# 10-RF_WIFI.net
KiCad netlist of a schematic drawn in Altium Designer
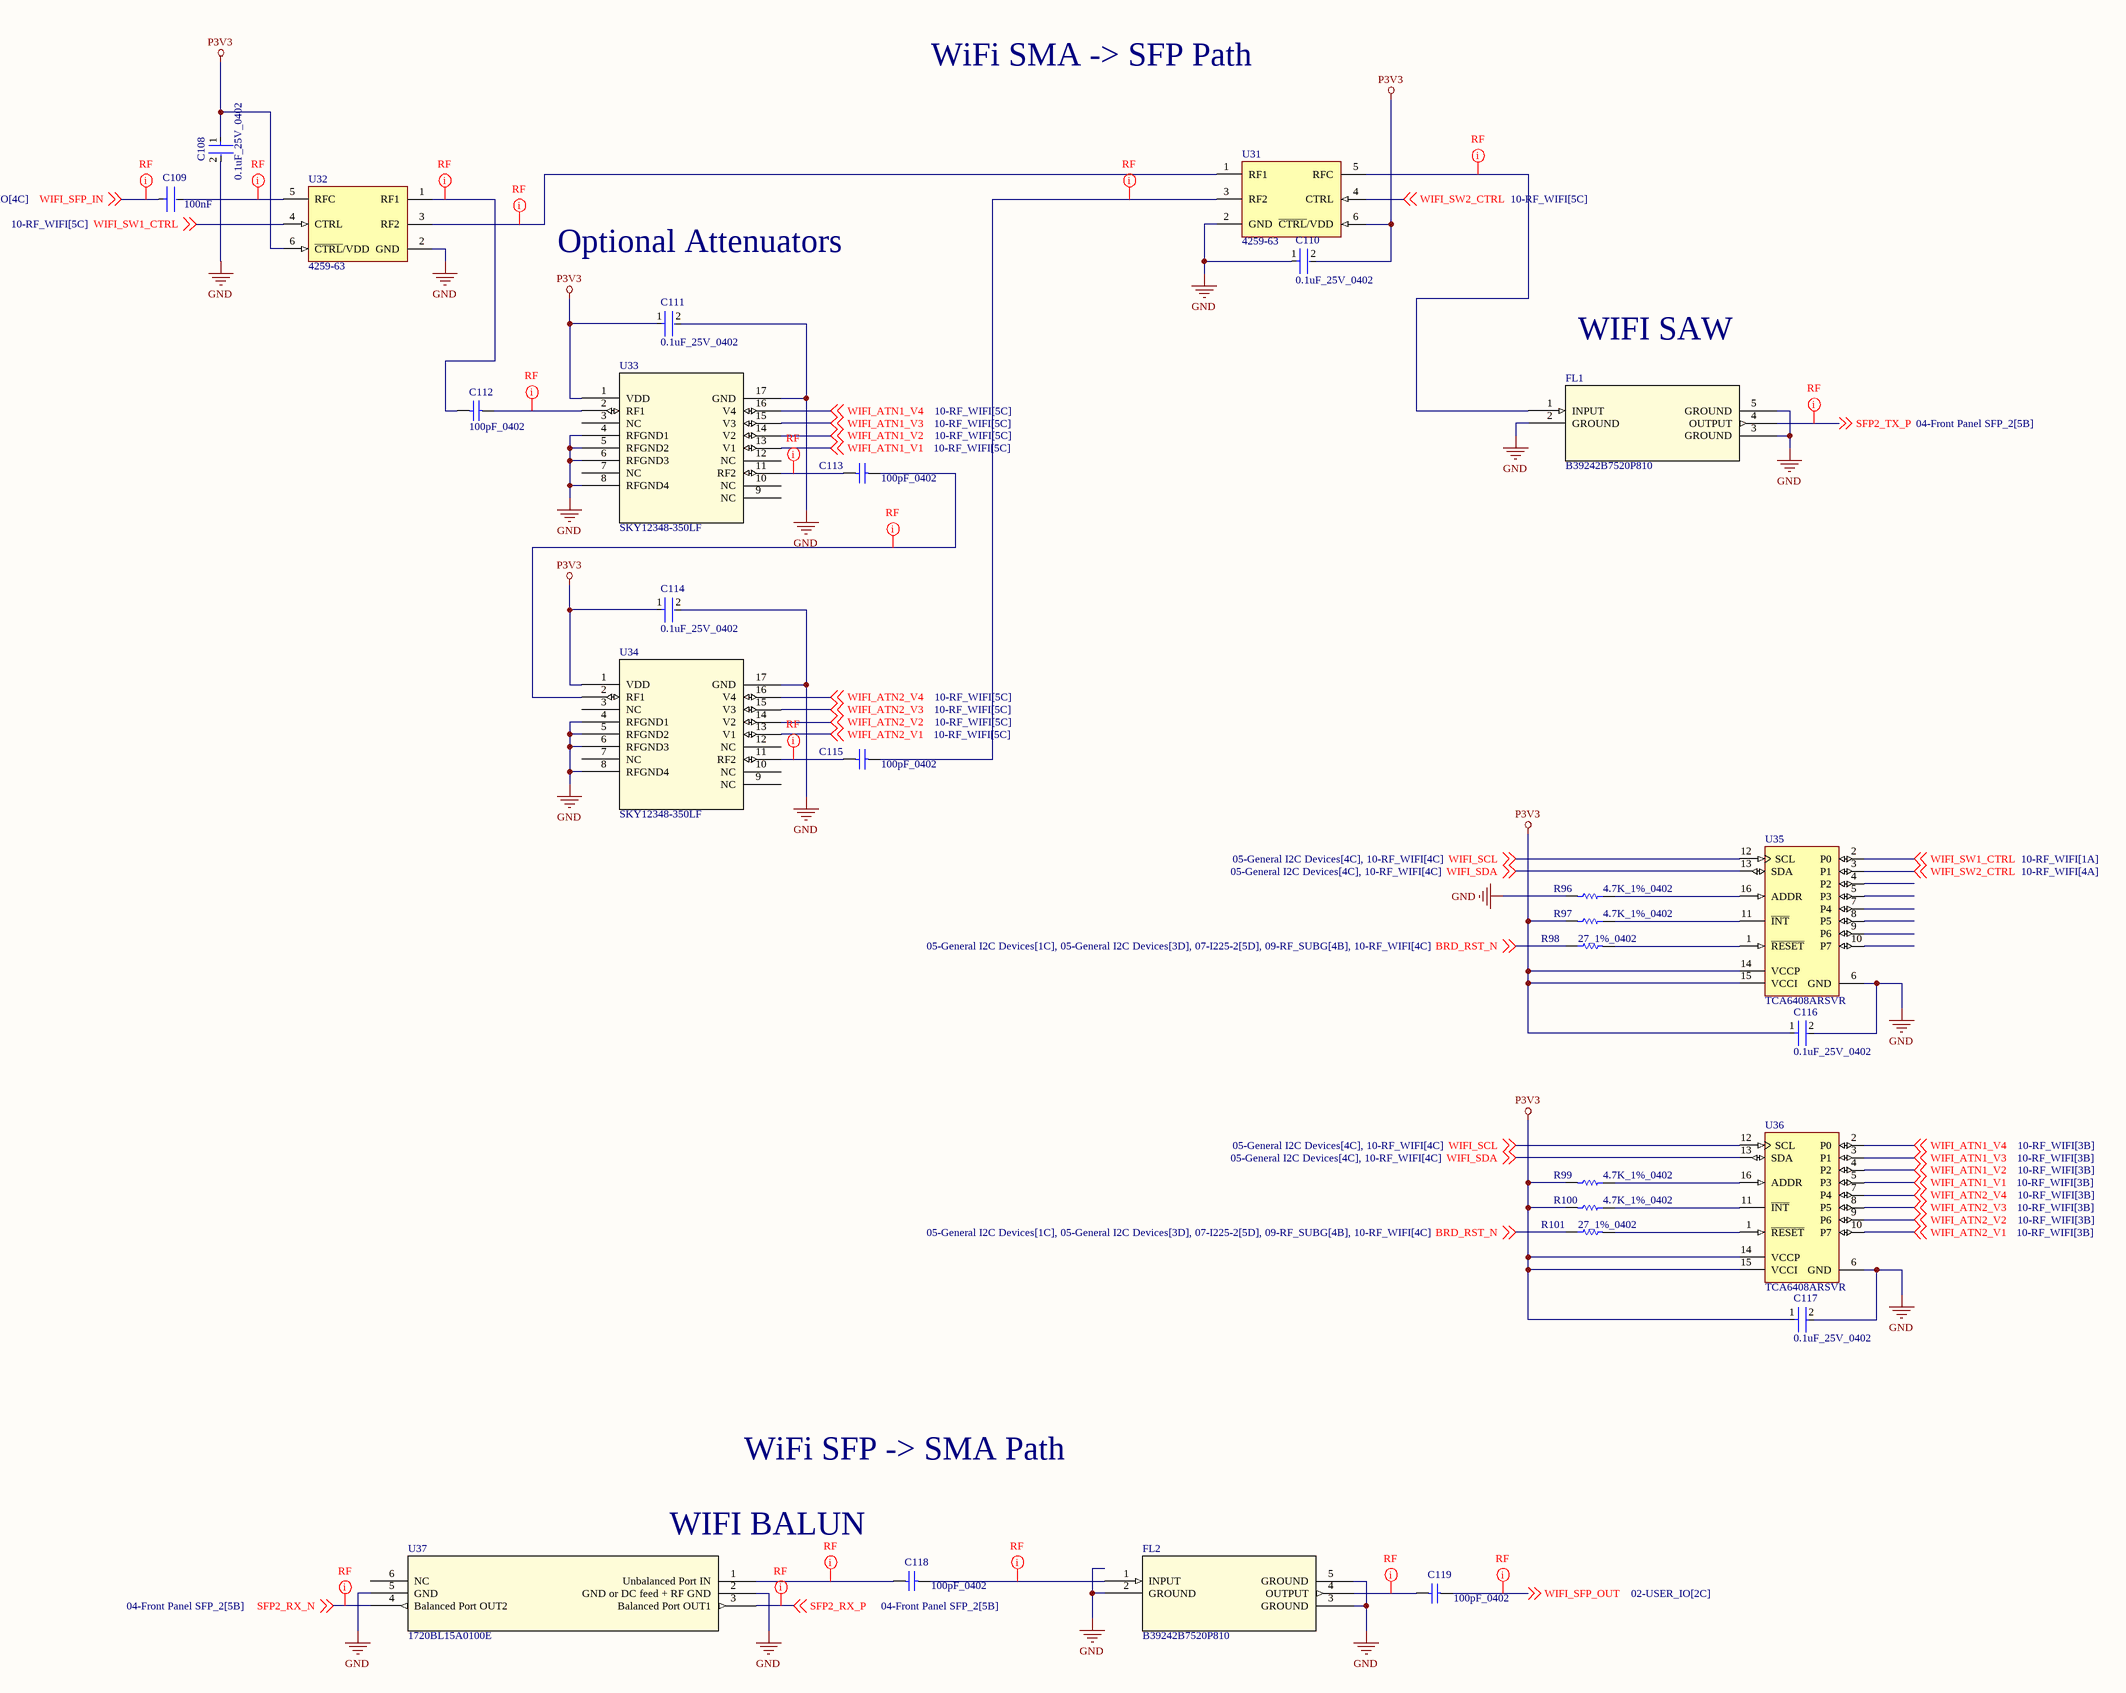
[diagram p0: 10-RF_WIFI.SchDoc]

(export (version "E")
  (design (tool "Eeschema 10.0.6"))
  (components
    (comp (ref "C108")
      (value "0.1uF_25V_0402")
      (footprint "FP-0402-L_1_0_1-W_0_5_0_1-IPC_C")
      (description "General Purpose Ceramic Capacitor, 0402, 100nF, 10%, X7R, 15%, 25V")
      (fields (field (name "VOLTAGE") "25V") (field (name "TOLERANCE") "10%"))
      (libsource (lib "Altium Content Vault") (part "b4654b650e69147ec39a6b967a45e02"))
    )
    (comp (ref "C109")
      (value "100nF")
      (footprint "FP-0402-L_1_0_0_05-W_0_5-IPC_B")
      (description "None")
      (fields (field (name "TOLERANCE") "10%"))
      (libsource (lib "") (part "b4654b650e69147ec39a6b967a45e02_1"))
    )
    (comp (ref "C110")
      (value "0.1uF_25V_0402")
      (footprint "FP-0402-L_1_0_1-W_0_5_0_1-IPC_C")
      (description "General Purpose Ceramic Capacitor, 0402, 100nF, 10%, X7R, 15%, 25V")
      (fields (field (name "VOLTAGE") "25V") (field (name "TOLERANCE") "10%"))
      (libsource (lib "Altium Content Vault") (part "b4654b650e69147ec39a6b967a45e02"))
    )
    (comp (ref "C111")
      (value "0.1uF_25V_0402")
      (footprint "FP-0402-L_1_0_1-W_0_5_0_1-IPC_C")
      (description "General Purpose Ceramic Capacitor, 0402, 100nF, 10%, X7R, 15%, 25V")
      (fields (field (name "VOLTAGE") "25V") (field (name "TOLERANCE") "10%"))
      (libsource (lib "Altium Content Vault") (part "b4654b650e69147ec39a6b967a45e02"))
    )
    (comp (ref "C112")
      (value "100pF_0402")
      (footprint "CAPC1005X55X25ML05T10")
      (fields (field (name "MANUFACTURER") "Murata") (field (name "PART NUMBER") "GRM1555C1H101JA01D"))
      (libsource (lib "Altium Content Vault") (part "CAP"))
    )
    (comp (ref "C113")
      (value "100pF_0402")
      (footprint "CAPC1005X55X25ML05T10")
      (fields (field (name "MANUFACTURER") "Murata") (field (name "PART NUMBER") "GRM1555C1H101JA01D"))
      (libsource (lib "Altium Content Vault") (part "CAP"))
    )
    (comp (ref "C114")
      (value "0.1uF_25V_0402")
      (footprint "FP-0402-L_1_0_1-W_0_5_0_1-IPC_C")
      (description "General Purpose Ceramic Capacitor, 0402, 100nF, 10%, X7R, 15%, 25V")
      (fields (field (name "VOLTAGE") "25V") (field (name "TOLERANCE") "10%"))
      (libsource (lib "Altium Content Vault") (part "b4654b650e69147ec39a6b967a45e02"))
    )
    (comp (ref "C115")
      (value "100pF_0402")
      (footprint "CAPC1005X55X25ML05T10")
      (fields (field (name "MANUFACTURER") "Murata") (field (name "PART NUMBER") "GRM1555C1H101JA01D"))
      (libsource (lib "Altium Content Vault") (part "CAP"))
    )
    (comp (ref "C116")
      (value "0.1uF_25V_0402")
      (footprint "FP-0402-L_1_0_1-W_0_5_0_1-IPC_C")
      (description "General Purpose Ceramic Capacitor, 0402, 100nF, 10%, X7R, 15%, 25V")
      (fields (field (name "VOLTAGE") "25V") (field (name "TOLERANCE") "10%"))
      (libsource (lib "Altium Content Vault") (part "b4654b650e69147ec39a6b967a45e02"))
    )
    (comp (ref "C117")
      (value "0.1uF_25V_0402")
      (footprint "FP-0402-L_1_0_1-W_0_5_0_1-IPC_C")
      (description "General Purpose Ceramic Capacitor, 0402, 100nF, 10%, X7R, 15%, 25V")
      (fields (field (name "VOLTAGE") "25V") (field (name "TOLERANCE") "10%"))
      (libsource (lib "Altium Content Vault") (part "b4654b650e69147ec39a6b967a45e02"))
    )
    (comp (ref "C118")
      (value "100pF_0402")
      (footprint "CAPC1005X55X25ML05T10")
      (fields (field (name "MANUFACTURER") "Murata") (field (name "PART NUMBER") "GRM1555C1H101JA01D"))
      (libsource (lib "Altium Content Vault") (part "CAP"))
    )
    (comp (ref "C119")
      (value "100pF_0402")
      (footprint "CAPC1005X55X25ML05T10")
      (fields (field (name "MANUFACTURER") "Murata") (field (name "PART NUMBER") "GRM1555C1H101JA01D"))
      (libsource (lib "Altium Content Vault") (part "CAP"))
    )
    (comp (ref "FL1")
      (value "B39242B7520P810")
      (footprint "SMD5_SAW-B7520_QUA")
      (description "No Description Available")
      (libsource (lib "B39242B7520P810") (part "B39242B7520P810"))
    )
    (comp (ref "FL2")
      (value "B39242B7520P810")
      (footprint "SMD5_SAW-B7520_QUA")
      (description "No Description Available")
      (libsource (lib "B39242B7520P810") (part "B39242B7520P810"))
    )
    (comp (ref "R96")
      (value "4.7K_1%_0402")
      (footprint "RESC1005X40X25NL10T10")
      (fields (field (name "MANUFACTURER") "Bourns") (field (name "PART NUMBER") "CR0402-FX-4701GLF"))
      (libsource (lib "Altium Content Vault") (part "RES"))
    )
    (comp (ref "R97")
      (value "4.7K_1%_0402")
      (footprint "RESC1005X40X25NL10T10")
      (fields (field (name "MANUFACTURER") "Bourns") (field (name "PART NUMBER") "CR0402-FX-4701GLF"))
      (libsource (lib "Altium Content Vault") (part "RES"))
    )
    (comp (ref "R98")
      (value "27_1%_0402")
      (footprint "RESC1005X40X25NL05T05")
      (fields (field (name "PART NUMBER") "CRCW040227R0FKED") (field (name "MANUFACTURER") "Vishay Dale"))
      (libsource (lib "Altium Content Vault") (part "RES"))
    )
    (comp (ref "R99")
      (value "4.7K_1%_0402")
      (footprint "RESC1005X40X25NL10T10")
      (fields (field (name "MANUFACTURER") "Bourns") (field (name "PART NUMBER") "CR0402-FX-4701GLF"))
      (libsource (lib "Altium Content Vault") (part "RES"))
    )
    (comp (ref "R100")
      (value "4.7K_1%_0402")
      (footprint "RESC1005X40X25NL10T10")
      (fields (field (name "MANUFACTURER") "Bourns") (field (name "PART NUMBER") "CR0402-FX-4701GLF"))
      (libsource (lib "Altium Content Vault") (part "RES"))
    )
    (comp (ref "R101")
      (value "27_1%_0402")
      (footprint "RESC1005X40X25NL05T05")
      (fields (field (name "PART NUMBER") "CRCW040227R0FKED") (field (name "MANUFACTURER") "Vishay Dale"))
      (libsource (lib "Altium Content Vault") (part "RES"))
    )
    (comp (ref "U31")
      (value "4259-63")
      (footprint "PERE-SC-70-6_M")
      (description "IC RF Switch SPDT, 50 Ohm, 6-Pin SC70, RoHS, Tape and Reel")
      (fields (field (name "MANUFACTURER") "Peregrine Semiconductor"))
      (libsource (lib "") (part "PERE-PE4259-6_1"))
    )
    (comp (ref "U32")
      (value "4259-63")
      (footprint "PERE-SC-70-6_M")
      (description "IC RF Switch SPDT, 50 Ohm, 6-Pin SC70, RoHS, Tape and Reel")
      (fields (field (name "MANUFACTURER") "Peregrine Semiconductor"))
      (libsource (lib "Altium Content Vault") (part "PERE-PE4259-6"))
    )
    (comp (ref "U33")
      (value "SKY12348-350LF")
      (footprint "SKY12348-350LF_SKY")
      (description "No Description Available")
      (libsource (lib "SKY12348-350LF") (part "SKY12348-350LF"))
    )
    (comp (ref "U34")
      (value "SKY12348-350LF")
      (footprint "SKY12348-350LF_SKY")
      (description "No Description Available")
      (libsource (lib "SKY12348-350LF") (part "SKY12348-350LF"))
    )
    (comp (ref "U35")
      (value "TCA6408ARSVR")
      (footprint "RSV0016A_V")
      (fields (field (name "MANUFACTURER") "Texas Instruments"))
      (libsource (lib "Altium Content Vault") (part "TI-TCA6408A-UQFN_RSV-16"))
    )
    (comp (ref "U36")
      (value "TCA6408ARSVR")
      (footprint "RSV0016A_V")
      (fields (field (name "MANUFACTURER") "Texas Instruments"))
      (libsource (lib "Altium Content Vault") (part "TI-TCA6408A-UQFN_RSV-16"))
    )
    (comp (ref "U37")
      (value "1720BL15A0100E")
      (footprint "SMT_15B0050E_JOT")
      (description "No Description Available")
      (libsource (lib "1720BL15A0100E") (part "1720BL15A0100E"))
    )
  )
  (nets
    (net (code "1") (name "BRD_RST_N") (class "Default")
      (node (ref "R101") (pin "1") (pinfunction "1_1") (pintype "passive"))
      (node (ref "R98") (pin "1") (pinfunction "1_1") (pintype "passive"))
    )
    (net (code "2") (name "GND") (class "Default")
      (node (ref "C108") (pin "2") (pinfunction "2_2") (pintype "passive"))
      (node (ref "C110") (pin "1") (pinfunction "1_1") (pintype "passive"))
      (node (ref "C111") (pin "2") (pinfunction "2_2") (pintype "passive"))
      (node (ref "C114") (pin "2") (pinfunction "2_2") (pintype "passive"))
      (node (ref "C116") (pin "2") (pinfunction "2_2") (pintype "passive"))
      (node (ref "C117") (pin "2") (pinfunction "2_2") (pintype "passive"))
      (node (ref "FL1") (pin "2") (pinfunction "GROUND_2") (pintype "power_in"))
      (node (ref "FL1") (pin "3") (pinfunction "GROUND_3") (pintype "power_in"))
      (node (ref "FL1") (pin "5") (pinfunction "GROUND_5") (pintype "power_in"))
      (node (ref "FL2") (pin "2") (pinfunction "GROUND_2") (pintype "power_in"))
      (node (ref "FL2") (pin "3") (pinfunction "GROUND_3") (pintype "power_in"))
      (node (ref "FL2") (pin "5") (pinfunction "GROUND_5") (pintype "power_in"))
      (node (ref "R96") (pin "2") (pinfunction "2_2") (pintype "passive"))
      (node (ref "U31") (pin "2") (pinfunction "GND_2") (pintype "power_in"))
      (node (ref "U32") (pin "2") (pinfunction "GND_2") (pintype "power_in"))
      (node (ref "U33") (pin "17") (pinfunction "GND_17") (pintype "power_in"))
      (node (ref "U33") (pin "4") (pinfunction "RFGND1_4") (pintype "power_in"))
      (node (ref "U33") (pin "5") (pinfunction "RFGND2_5") (pintype "power_in"))
      (node (ref "U33") (pin "6") (pinfunction "RFGND3_6") (pintype "power_in"))
      (node (ref "U33") (pin "8") (pinfunction "RFGND4_8") (pintype "power_in"))
      (node (ref "U34") (pin "17") (pinfunction "GND_17") (pintype "power_in"))
      (node (ref "U34") (pin "4") (pinfunction "RFGND1_4") (pintype "power_in"))
      (node (ref "U34") (pin "5") (pinfunction "RFGND2_5") (pintype "power_in"))
      (node (ref "U34") (pin "6") (pinfunction "RFGND3_6") (pintype "power_in"))
      (node (ref "U34") (pin "8") (pinfunction "RFGND4_8") (pintype "power_in"))
      (node (ref "U35") (pin "6") (pinfunction "GND_6") (pintype "power_in"))
      (node (ref "U36") (pin "6") (pinfunction "GND_6") (pintype "power_in"))
      (node (ref "U37") (pin "2") (pinfunction "GND_or_DC_feed_+_RF_GND_2") (pintype "power_in"))
      (node (ref "U37") (pin "5") (pinfunction "GND_5") (pintype "power_in"))
    )
    (net (code "3") (name "Net-(FL1-INPUT)") (class "Default")
      (node (ref "FL1") (pin "1") (pinfunction "INPUT_1") (pintype "input"))
      (node (ref "U31") (pin "5") (pinfunction "RFC_5") (pintype "passive"))
    )
    (net (code "4") (name "Net-(FL2-INPUT)") (class "Default")
      (node (ref "C118") (pin "2") (pinfunction "2_2") (pintype "passive"))
      (node (ref "FL2") (pin "1") (pinfunction "INPUT_1") (pintype "input"))
    )
    (net (code "5") (name "Net-(FL2-OUTPUT)") (class "Default")
      (node (ref "C119") (pin "1") (pinfunction "1_1") (pintype "passive"))
      (node (ref "FL2") (pin "4") (pinfunction "OUTPUT_4") (pintype "output"))
    )
    (net (code "6") (name "Net-(U31-RF1)") (class "Default")
      (node (ref "U31") (pin "1") (pinfunction "RF1_1") (pintype "passive"))
      (node (ref "U32") (pin "3") (pinfunction "RF2_3") (pintype "passive"))
    )
    (net (code "7") (name "Net-(U31-RF2)") (class "Default")
      (node (ref "C115") (pin "2") (pinfunction "2_2") (pintype "passive"))
      (node (ref "U31") (pin "3") (pinfunction "RF2_3") (pintype "passive"))
    )
    (net (code "8") (name "Net-(U32-RF1)") (class "Default")
      (node (ref "C112") (pin "1") (pinfunction "1_1") (pintype "passive"))
      (node (ref "U32") (pin "1") (pinfunction "RF1_1") (pintype "passive"))
    )
    (net (code "9") (name "Net-(U32-RFC)") (class "Default")
      (node (ref "C109") (pin "2") (pinfunction "2_2") (pintype "passive"))
      (node (ref "U32") (pin "5") (pinfunction "RFC_5") (pintype "passive"))
    )
    (net (code "10") (name "Net-(U33-RF1)") (class "Default")
      (node (ref "C112") (pin "2") (pinfunction "2_2") (pintype "passive"))
      (node (ref "U33") (pin "2") (pinfunction "RF1_2") (pintype "bidirectional"))
    )
    (net (code "11") (name "Net-(U33-RF2)") (class "Default")
      (node (ref "C113") (pin "1") (pinfunction "1_1") (pintype "passive"))
      (node (ref "U33") (pin "11") (pinfunction "RF2_11") (pintype "bidirectional"))
    )
    (net (code "12") (name "Net-(U34-RF1)") (class "Default")
      (node (ref "C113") (pin "2") (pinfunction "2_2") (pintype "passive"))
      (node (ref "U34") (pin "2") (pinfunction "RF1_2") (pintype "bidirectional"))
    )
    (net (code "13") (name "Net-(U34-RF2)") (class "Default")
      (node (ref "C115") (pin "1") (pinfunction "1_1") (pintype "passive"))
      (node (ref "U34") (pin "11") (pinfunction "RF2_11") (pintype "bidirectional"))
    )
    (net (code "14") (name "Net-(U35-ADDR)") (class "Default")
      (node (ref "R96") (pin "1") (pinfunction "1_1") (pintype "passive"))
      (node (ref "U35") (pin "16") (pinfunction "ADDR_16") (pintype "input"))
    )
    (net (code "15") (name "Net-(U35-~{INT})") (class "Default")
      (node (ref "R97") (pin "1") (pinfunction "1_1") (pintype "passive"))
      (node (ref "U35") (pin "11") (pinfunction "~{INT}_11") (pintype "open_collector"))
    )
    (net (code "16") (name "Net-(U35-~{RESET})") (class "Default")
      (node (ref "R98") (pin "2") (pinfunction "2_2") (pintype "passive"))
      (node (ref "U35") (pin "1") (pinfunction "~{RESET}_1") (pintype "input"))
    )
    (net (code "17") (name "Net-(U36-ADDR)") (class "Default")
      (node (ref "R99") (pin "1") (pinfunction "1_1") (pintype "passive"))
      (node (ref "U36") (pin "16") (pinfunction "ADDR_16") (pintype "input"))
    )
    (net (code "18") (name "Net-(U36-~{INT})") (class "Default")
      (node (ref "R100") (pin "1") (pinfunction "1_1") (pintype "passive"))
      (node (ref "U36") (pin "11") (pinfunction "~{INT}_11") (pintype "open_collector"))
    )
    (net (code "19") (name "Net-(U36-~{RESET})") (class "Default")
      (node (ref "R101") (pin "2") (pinfunction "2_2") (pintype "passive"))
      (node (ref "U36") (pin "1") (pinfunction "~{RESET}_1") (pintype "input"))
    )
    (net (code "20") (name "Net-(U37-Unbalanced_Port_IN)") (class "Default")
      (node (ref "C118") (pin "1") (pinfunction "1_1") (pintype "passive"))
      (node (ref "U37") (pin "1") (pinfunction "Unbalanced_Port_IN_1") (pintype "passive"))
    )
    (net (code "21") (name "P3V3") (class "Default")
      (node (ref "C108") (pin "1") (pinfunction "1_1") (pintype "passive"))
      (node (ref "C110") (pin "2") (pinfunction "2_2") (pintype "passive"))
      (node (ref "C111") (pin "1") (pinfunction "1_1") (pintype "passive"))
      (node (ref "C114") (pin "1") (pinfunction "1_1") (pintype "passive"))
      (node (ref "C116") (pin "1") (pinfunction "1_1") (pintype "passive"))
      (node (ref "C117") (pin "1") (pinfunction "1_1") (pintype "passive"))
      (node (ref "R100") (pin "2") (pinfunction "2_2") (pintype "passive"))
      (node (ref "R97") (pin "2") (pinfunction "2_2") (pintype "passive"))
      (node (ref "R99") (pin "2") (pinfunction "2_2") (pintype "passive"))
      (node (ref "U31") (pin "6") (pinfunction "~{CTRL}/VDD_6") (pintype "input"))
      (node (ref "U32") (pin "6") (pinfunction "~{CTRL}/VDD_6") (pintype "input"))
      (node (ref "U33") (pin "1") (pinfunction "VDD_1") (pintype "power_in"))
      (node (ref "U34") (pin "1") (pinfunction "VDD_1") (pintype "power_in"))
      (node (ref "U35") (pin "14") (pinfunction "VCCP_14") (pintype "power_in"))
      (node (ref "U35") (pin "15") (pinfunction "VCCI_15") (pintype "power_in"))
      (node (ref "U36") (pin "14") (pinfunction "VCCP_14") (pintype "power_in"))
      (node (ref "U36") (pin "15") (pinfunction "VCCI_15") (pintype "power_in"))
    )
    (net (code "22") (name "SFP2_RX_N") (class "Default")
      (node (ref "U37") (pin "4") (pinfunction "Balanced_Port_OUT2_4") (pintype "output"))
    )
    (net (code "23") (name "SFP2_RX_P") (class "Default")
      (node (ref "U37") (pin "3") (pinfunction "Balanced_Port_OUT1_3") (pintype "output"))
    )
    (net (code "24") (name "SFP2_TX_P") (class "Default")
      (node (ref "FL1") (pin "4") (pinfunction "OUTPUT_4") (pintype "output"))
    )
    (net (code "25") (name "WIFI_ATN1_V1") (class "Default")
      (node (ref "U33") (pin "13") (pinfunction "V1_13") (pintype "bidirectional"))
      (node (ref "U36") (pin "5") (pinfunction "P3_5") (pintype "bidirectional"))
    )
    (net (code "26") (name "WIFI_ATN1_V2") (class "Default")
      (node (ref "U33") (pin "14") (pinfunction "V2_14") (pintype "bidirectional"))
      (node (ref "U36") (pin "4") (pinfunction "P2_4") (pintype "bidirectional"))
    )
    (net (code "27") (name "WIFI_ATN1_V3") (class "Default")
      (node (ref "U33") (pin "15") (pinfunction "V3_15") (pintype "bidirectional"))
      (node (ref "U36") (pin "3") (pinfunction "P1_3") (pintype "bidirectional"))
    )
    (net (code "28") (name "WIFI_ATN1_V4") (class "Default")
      (node (ref "U33") (pin "16") (pinfunction "V4_16") (pintype "bidirectional"))
      (node (ref "U36") (pin "2") (pinfunction "P0_2") (pintype "bidirectional"))
    )
    (net (code "29") (name "WIFI_ATN2_V1") (class "Default")
      (node (ref "U34") (pin "13") (pinfunction "V1_13") (pintype "bidirectional"))
      (node (ref "U36") (pin "10") (pinfunction "P7_10") (pintype "bidirectional"))
    )
    (net (code "30") (name "WIFI_ATN2_V2") (class "Default")
      (node (ref "U34") (pin "14") (pinfunction "V2_14") (pintype "bidirectional"))
      (node (ref "U36") (pin "9") (pinfunction "P6_9") (pintype "bidirectional"))
    )
    (net (code "31") (name "WIFI_ATN2_V3") (class "Default")
      (node (ref "U34") (pin "15") (pinfunction "V3_15") (pintype "bidirectional"))
      (node (ref "U36") (pin "8") (pinfunction "P5_8") (pintype "bidirectional"))
    )
    (net (code "32") (name "WIFI_ATN2_V4") (class "Default")
      (node (ref "U34") (pin "16") (pinfunction "V4_16") (pintype "bidirectional"))
      (node (ref "U36") (pin "7") (pinfunction "P4_7") (pintype "bidirectional"))
    )
    (net (code "33") (name "WIFI_SCL") (class "Default")
      (node (ref "U35") (pin "12") (pinfunction "SCL_12") (pintype "input"))
      (node (ref "U36") (pin "12") (pinfunction "SCL_12") (pintype "input"))
    )
    (net (code "34") (name "WIFI_SDA") (class "Default")
      (node (ref "U35") (pin "13") (pinfunction "SDA_13") (pintype "bidirectional"))
      (node (ref "U36") (pin "13") (pinfunction "SDA_13") (pintype "bidirectional"))
    )
    (net (code "35") (name "WIFI_SFP_IN") (class "Default")
      (node (ref "C109") (pin "1") (pinfunction "1_1") (pintype "passive"))
    )
    (net (code "36") (name "WIFI_SFP_OUT") (class "Default")
      (node (ref "C119") (pin "2") (pinfunction "2_2") (pintype "passive"))
    )
    (net (code "37") (name "WIFI_SW1_CTRL") (class "Default")
      (node (ref "U32") (pin "4") (pinfunction "CTRL_4") (pintype "input"))
      (node (ref "U35") (pin "2") (pinfunction "P0_2") (pintype "bidirectional"))
    )
    (net (code "38") (name "WIFI_SW2_CTRL") (class "Default")
      (node (ref "U31") (pin "4") (pinfunction "CTRL_4") (pintype "input"))
      (node (ref "U35") (pin "3") (pinfunction "P1_3") (pintype "bidirectional"))
    )
    (net (code "39") (name "unconnected-(U33-NC-Pad3)") (class "Default")
      (node (ref "U33") (pin "3") (pinfunction "NC_3") (pintype "passive"))
    )
    (net (code "40") (name "unconnected-(U33-NC-Pad7)") (class "Default")
      (node (ref "U33") (pin "7") (pinfunction "NC_7") (pintype "passive"))
    )
    (net (code "41") (name "unconnected-(U33-NC-Pad9)") (class "Default")
      (node (ref "U33") (pin "9") (pinfunction "NC_9") (pintype "passive"))
    )
    (net (code "42") (name "unconnected-(U33-NC-Pad10)") (class "Default")
      (node (ref "U33") (pin "10") (pinfunction "NC_10") (pintype "passive"))
    )
    (net (code "43") (name "unconnected-(U33-NC-Pad12)") (class "Default")
      (node (ref "U33") (pin "12") (pinfunction "NC_12") (pintype "passive"))
    )
    (net (code "44") (name "unconnected-(U34-NC-Pad3)") (class "Default")
      (node (ref "U34") (pin "3") (pinfunction "NC_3") (pintype "passive"))
    )
    (net (code "45") (name "unconnected-(U34-NC-Pad7)") (class "Default")
      (node (ref "U34") (pin "7") (pinfunction "NC_7") (pintype "passive"))
    )
    (net (code "46") (name "unconnected-(U34-NC-Pad9)") (class "Default")
      (node (ref "U34") (pin "9") (pinfunction "NC_9") (pintype "passive"))
    )
    (net (code "47") (name "unconnected-(U34-NC-Pad10)") (class "Default")
      (node (ref "U34") (pin "10") (pinfunction "NC_10") (pintype "passive"))
    )
    (net (code "48") (name "unconnected-(U34-NC-Pad12)") (class "Default")
      (node (ref "U34") (pin "12") (pinfunction "NC_12") (pintype "passive"))
    )
    (net (code "49") (name "unconnected-(U35-P2-Pad4)") (class "Default")
      (node (ref "U35") (pin "4") (pinfunction "P2_4") (pintype "bidirectional"))
    )
    (net (code "50") (name "unconnected-(U35-P3-Pad5)") (class "Default")
      (node (ref "U35") (pin "5") (pinfunction "P3_5") (pintype "bidirectional"))
    )
    (net (code "51") (name "unconnected-(U35-P4-Pad7)") (class "Default")
      (node (ref "U35") (pin "7") (pinfunction "P4_7") (pintype "bidirectional"))
    )
    (net (code "52") (name "unconnected-(U35-P5-Pad8)") (class "Default")
      (node (ref "U35") (pin "8") (pinfunction "P5_8") (pintype "bidirectional"))
    )
    (net (code "53") (name "unconnected-(U35-P6-Pad9)") (class "Default")
      (node (ref "U35") (pin "9") (pinfunction "P6_9") (pintype "bidirectional"))
    )
    (net (code "54") (name "unconnected-(U35-P7-Pad10)") (class "Default")
      (node (ref "U35") (pin "10") (pinfunction "P7_10") (pintype "bidirectional"))
    )
    (net (code "55") (name "unconnected-(U37-NC-Pad6)") (class "Default")
      (node (ref "U37") (pin "6") (pinfunction "NC_6") (pintype "passive"))
    )
  )
)
